# 3_CENR-40_PCA-10_NBU-1012_PWF_SIMMER_EMM.net
KiCad netlist of a schematic drawn in Altium Designer
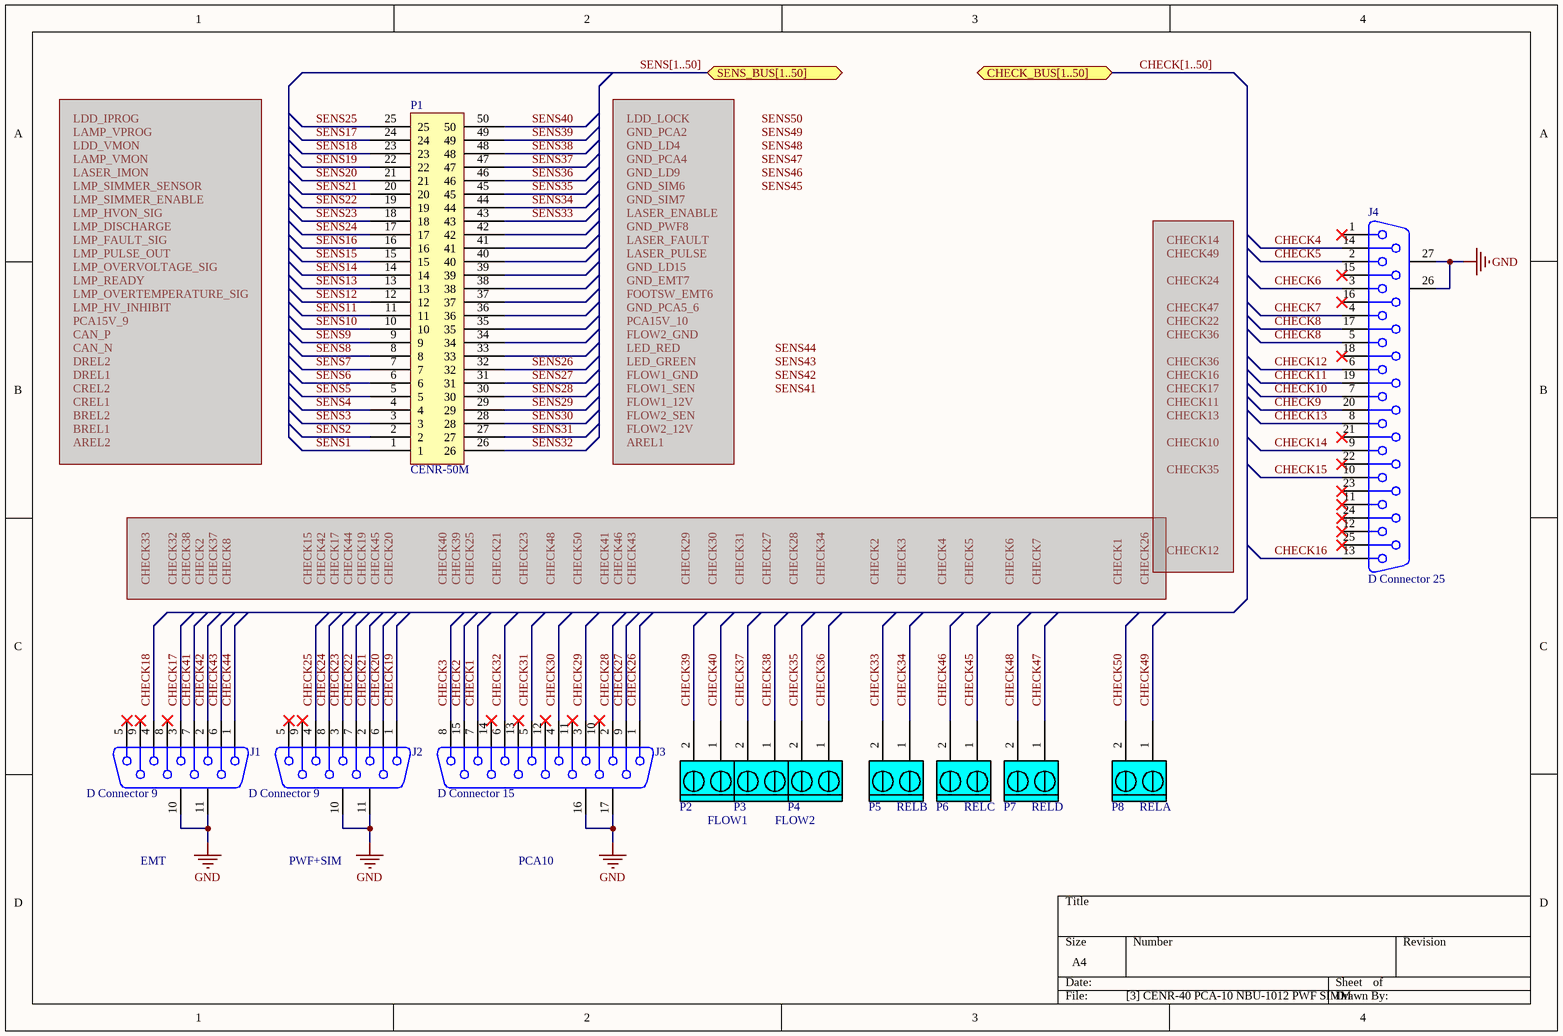
[diagram p0: [3] CENR-40 PCA-10 NBU-1012 PWF SIMMER EMMITER.SchDoc]

(export (version "E")
  (design (tool "Eeschema 10.0.6"))
  (components
    (comp (ref "J1")
      (value "D Connector 9")
      (footprint "DSUB1.385-2H9F")
      (description "Receptacle Assembly, 9 Position, Right Angle")
      (fields (field (name "PUBLISHER") "Altium Limited"))
      (libsource (lib "Connectors") (part "D Connector 9"))
    )
    (comp (ref "J2")
      (value "D Connector 9")
      (footprint "DSUB1.385-2H9M")
      (description "Receptacle Assembly, 9 Position, Right Angle")
      (fields (field (name "PUBLISHER") "Altium Limited"))
      (libsource (lib "Connectors") (part "D Connector 9"))
    )
    (comp (ref "J3")
      (value "D Connector 15")
      (footprint "DSUB1.385-2H15M")
      (description "Receptacle Assembly, 15 Position, Right Angle")
      (fields (field (name "PUBLISHER") "Altium Limited"))
      (libsource (lib "Connectors") (part "D Connector 15"))
    )
    (comp (ref "J4")
      (value "D Connector 25")
      (footprint "DSUB1.385-2H25A-F")
      (description "Receptacle Assembly, 25 Position, Right Angle")
      (fields (field (name "PUBLISHER") "Altium Limited"))
      (libsource (lib "Connectors") (part "D Connector 25"))
    )
    (comp (ref "P1")
      (value "CENR-50M")
      (footprint "CENR-50M")
      (libsource (lib "Connectors") (part "CENR-50M"))
    )
    (comp (ref "P2")
      (value "DG340-3.81")
      (footprint "DG340-3.81-02P-00A(H)")
      (description "Terminal block")
      (libsource (lib "Connectors") (part "DG340-3.81-02P"))
    )
    (comp (ref "P3")
      (value "DG340-3.81")
      (footprint "DG340-3.81-02P-00A(H)")
      (description "Terminal block")
      (libsource (lib "Connectors") (part "DG340-3.81-02P"))
    )
    (comp (ref "P4")
      (value "DG340-3.81")
      (footprint "DG340-3.81-02P-00A(H)")
      (description "Terminal block")
      (libsource (lib "Connectors") (part "DG340-3.81-02P"))
    )
    (comp (ref "P5")
      (value "DG340-3.81")
      (footprint "DG340-3.81-02P-00A(H)")
      (description "Terminal block")
      (libsource (lib "Connectors") (part "DG340-3.81-02P"))
    )
    (comp (ref "P6")
      (value "DG340-3.81")
      (footprint "DG340-3.81-02P-00A(H)")
      (description "Terminal block")
      (libsource (lib "Connectors") (part "DG340-3.81-02P"))
    )
    (comp (ref "P7")
      (value "DG340-3.81")
      (footprint "DG340-3.81-02P-00A(H)")
      (description "Terminal block")
      (libsource (lib "Connectors") (part "DG340-3.81-02P"))
    )
    (comp (ref "P8")
      (value "DG340-3.81")
      (footprint "DG340-3.81-02P-00A(H)")
      (description "Terminal block")
      (libsource (lib "Connectors") (part "DG340-3.81-02P"))
    )
  )
  (nets
    (net (code "7") (name "/CHECK1") (class "Default")
      (node (ref "J3") (pin "7") (pinfunction "7_7") (pintype "passive"))
    )
    (net (code "8") (name "/CHECK2") (class "Default")
      (node (ref "J3") (pin "15") (pinfunction "15_15") (pintype "passive"))
    )
    (net (code "9") (name "/CHECK3") (class "Default")
      (node (ref "J3") (pin "8") (pinfunction "8_8") (pintype "passive"))
    )
    (net (code "10") (name "/CHECK4") (class "Default")
      (node (ref "J4") (pin "14") (pinfunction "14_14") (pintype "passive"))
    )
    (net (code "11") (name "/CHECK5") (class "Default")
      (node (ref "J4") (pin "2") (pinfunction "2_2") (pintype "passive"))
    )
    (net (code "12") (name "/CHECK6") (class "Default")
      (node (ref "J4") (pin "3") (pinfunction "3_3") (pintype "passive"))
    )
    (net (code "13") (name "/CHECK7") (class "Default")
      (node (ref "J4") (pin "4") (pinfunction "4_4") (pintype "passive"))
    )
    (net (code "14") (name "/CHECK8") (class "Default")
      (node (ref "J4") (pin "17") (pinfunction "17_17") (pintype "passive"))
      (node (ref "J4") (pin "5") (pinfunction "5_5") (pintype "passive"))
    )
    (net (code "15") (name "/CHECK9") (class "Default")
      (node (ref "J4") (pin "20") (pinfunction "20_20") (pintype "passive"))
    )
    (net (code "16") (name "/CHECK10") (class "Default")
      (node (ref "J4") (pin "7") (pinfunction "7_7") (pintype "passive"))
    )
    (net (code "17") (name "/CHECK11") (class "Default")
      (node (ref "J4") (pin "19") (pinfunction "19_19") (pintype "passive"))
    )
    (net (code "18") (name "/CHECK12") (class "Default")
      (node (ref "J4") (pin "6") (pinfunction "6_6") (pintype "passive"))
    )
    (net (code "19") (name "/CHECK13") (class "Default")
      (node (ref "J4") (pin "8") (pinfunction "8_8") (pintype "passive"))
    )
    (net (code "20") (name "/CHECK14") (class "Default")
      (node (ref "J4") (pin "9") (pinfunction "9_9") (pintype "passive"))
    )
    (net (code "21") (name "/CHECK15") (class "Default")
      (node (ref "J4") (pin "10") (pinfunction "10_10") (pintype "passive"))
    )
    (net (code "22") (name "/CHECK16") (class "Default")
      (node (ref "J4") (pin "13") (pinfunction "13_13") (pintype "passive"))
    )
    (net (code "23") (name "/CHECK17") (class "Default")
      (node (ref "J1") (pin "3") (pinfunction "3_3") (pintype "passive"))
    )
    (net (code "24") (name "/CHECK18") (class "Default")
      (node (ref "J1") (pin "4") (pinfunction "4_4") (pintype "passive"))
    )
    (net (code "25") (name "/CHECK19") (class "Default")
      (node (ref "J2") (pin "1") (pinfunction "1_1") (pintype "passive"))
    )
    (net (code "26") (name "/CHECK20") (class "Default")
      (node (ref "J2") (pin "6") (pinfunction "6_6") (pintype "passive"))
    )
    (net (code "27") (name "/CHECK21") (class "Default")
      (node (ref "J2") (pin "2") (pinfunction "2_2") (pintype "passive"))
    )
    (net (code "28") (name "/CHECK22") (class "Default")
      (node (ref "J2") (pin "7") (pinfunction "7_7") (pintype "passive"))
    )
    (net (code "29") (name "/CHECK23") (class "Default")
      (node (ref "J2") (pin "3") (pinfunction "3_3") (pintype "passive"))
    )
    (net (code "30") (name "/CHECK24") (class "Default")
      (node (ref "J2") (pin "8") (pinfunction "8_8") (pintype "passive"))
    )
    (net (code "31") (name "/CHECK25") (class "Default")
      (node (ref "J2") (pin "4") (pinfunction "4_4") (pintype "passive"))
    )
    (net (code "32") (name "/CHECK26") (class "Default")
      (node (ref "J3") (pin "1") (pinfunction "1_1") (pintype "passive"))
    )
    (net (code "33") (name "/CHECK27") (class "Default")
      (node (ref "J3") (pin "9") (pinfunction "9_9") (pintype "passive"))
    )
    (net (code "34") (name "/CHECK28") (class "Default")
      (node (ref "J3") (pin "2") (pinfunction "2_2") (pintype "passive"))
    )
    (net (code "35") (name "/CHECK29") (class "Default")
      (node (ref "J3") (pin "3") (pinfunction "3_3") (pintype "passive"))
    )
    (net (code "36") (name "/CHECK30") (class "Default")
      (node (ref "J3") (pin "4") (pinfunction "4_4") (pintype "passive"))
    )
    (net (code "37") (name "/CHECK31") (class "Default")
      (node (ref "J3") (pin "5") (pinfunction "5_5") (pintype "passive"))
    )
    (net (code "38") (name "/CHECK32") (class "Default")
      (node (ref "J3") (pin "6") (pinfunction "6_6") (pintype "passive"))
    )
    (net (code "39") (name "/CHECK33") (class "Default")
      (node (ref "P5") (pin "2") (pinfunction "2_2") (pintype "passive"))
    )
    (net (code "40") (name "/CHECK34") (class "Default")
      (node (ref "P5") (pin "1") (pinfunction "1_1") (pintype "passive"))
    )
    (net (code "41") (name "/CHECK35") (class "Default")
      (node (ref "P4") (pin "2") (pinfunction "2_2") (pintype "passive"))
    )
    (net (code "42") (name "/CHECK36") (class "Default")
      (node (ref "P4") (pin "1") (pinfunction "1_1") (pintype "passive"))
    )
    (net (code "43") (name "/CHECK37") (class "Default")
      (node (ref "P3") (pin "2") (pinfunction "2_2") (pintype "passive"))
    )
    (net (code "44") (name "/CHECK38") (class "Default")
      (node (ref "P3") (pin "1") (pinfunction "1_1") (pintype "passive"))
    )
    (net (code "45") (name "/CHECK39") (class "Default")
      (node (ref "P2") (pin "2") (pinfunction "2_2") (pintype "passive"))
    )
    (net (code "46") (name "/CHECK40") (class "Default")
      (node (ref "P2") (pin "1") (pinfunction "1_1") (pintype "passive"))
    )
    (net (code "47") (name "/CHECK41") (class "Default")
      (node (ref "J1") (pin "7") (pinfunction "7_7") (pintype "passive"))
    )
    (net (code "48") (name "/CHECK42") (class "Default")
      (node (ref "J1") (pin "2") (pinfunction "2_2") (pintype "passive"))
    )
    (net (code "49") (name "/CHECK43") (class "Default")
      (node (ref "J1") (pin "6") (pinfunction "6_6") (pintype "passive"))
    )
    (net (code "50") (name "/CHECK44") (class "Default")
      (node (ref "J1") (pin "1") (pinfunction "1_1") (pintype "passive"))
    )
    (net (code "51") (name "/CHECK45") (class "Default")
      (node (ref "P6") (pin "1") (pinfunction "1_1") (pintype "passive"))
    )
    (net (code "52") (name "/CHECK46") (class "Default")
      (node (ref "P6") (pin "2") (pinfunction "2_2") (pintype "passive"))
    )
    (net (code "53") (name "/CHECK47") (class "Default")
      (node (ref "P7") (pin "1") (pinfunction "1_1") (pintype "passive"))
    )
    (net (code "54") (name "/CHECK48") (class "Default")
      (node (ref "P7") (pin "2") (pinfunction "2_2") (pintype "passive"))
    )
    (net (code "55") (name "/CHECK49") (class "Default")
      (node (ref "P8") (pin "1") (pinfunction "1_1") (pintype "passive"))
    )
    (net (code "56") (name "/CHECK50") (class "Default")
      (node (ref "P8") (pin "2") (pinfunction "2_2") (pintype "passive"))
    )
    (net (code "102") (name "/SENS1") (class "Default")
      (node (ref "P1") (pin "1") (pinfunction "1_1") (pintype "passive"))
    )
    (net (code "103") (name "/SENS2") (class "Default")
      (node (ref "P1") (pin "2") (pinfunction "2_2") (pintype "passive"))
    )
    (net (code "104") (name "/SENS3") (class "Default")
      (node (ref "P1") (pin "3") (pinfunction "3_3") (pintype "passive"))
    )
    (net (code "105") (name "/SENS4") (class "Default")
      (node (ref "P1") (pin "4") (pinfunction "4_4") (pintype "passive"))
    )
    (net (code "106") (name "/SENS5") (class "Default")
      (node (ref "P1") (pin "5") (pinfunction "5_5") (pintype "passive"))
    )
    (net (code "107") (name "/SENS6") (class "Default")
      (node (ref "P1") (pin "6") (pinfunction "6_6") (pintype "passive"))
    )
    (net (code "108") (name "/SENS7") (class "Default")
      (node (ref "P1") (pin "7") (pinfunction "7_7") (pintype "passive"))
    )
    (net (code "109") (name "/SENS8") (class "Default")
      (node (ref "P1") (pin "8") (pinfunction "8_8") (pintype "passive"))
    )
    (net (code "110") (name "/SENS9") (class "Default")
      (node (ref "P1") (pin "9") (pinfunction "9_9") (pintype "passive"))
    )
    (net (code "111") (name "/SENS10") (class "Default")
      (node (ref "P1") (pin "10") (pinfunction "10_10") (pintype "passive"))
    )
    (net (code "112") (name "/SENS11") (class "Default")
      (node (ref "P1") (pin "11") (pinfunction "11_11") (pintype "passive"))
    )
    (net (code "113") (name "/SENS12") (class "Default")
      (node (ref "P1") (pin "12") (pinfunction "12_12") (pintype "passive"))
    )
    (net (code "114") (name "/SENS13") (class "Default")
      (node (ref "P1") (pin "13") (pinfunction "13_13") (pintype "passive"))
    )
    (net (code "115") (name "/SENS14") (class "Default")
      (node (ref "P1") (pin "14") (pinfunction "14_14") (pintype "passive"))
    )
    (net (code "116") (name "/SENS15") (class "Default")
      (node (ref "P1") (pin "15") (pinfunction "15_15") (pintype "passive"))
    )
    (net (code "117") (name "/SENS16") (class "Default")
      (node (ref "P1") (pin "16") (pinfunction "16_16") (pintype "passive"))
    )
    (net (code "118") (name "/SENS17") (class "Default")
      (node (ref "P1") (pin "24") (pinfunction "24_24") (pintype "passive"))
    )
    (net (code "119") (name "/SENS18") (class "Default")
      (node (ref "P1") (pin "23") (pinfunction "23_23") (pintype "passive"))
    )
    (net (code "120") (name "/SENS19") (class "Default")
      (node (ref "P1") (pin "22") (pinfunction "22_22") (pintype "passive"))
    )
    (net (code "121") (name "/SENS20") (class "Default")
      (node (ref "P1") (pin "21") (pinfunction "21_21") (pintype "passive"))
    )
    (net (code "122") (name "/SENS21") (class "Default")
      (node (ref "P1") (pin "20") (pinfunction "20_20") (pintype "passive"))
    )
    (net (code "123") (name "/SENS22") (class "Default")
      (node (ref "P1") (pin "19") (pinfunction "19_19") (pintype "passive"))
    )
    (net (code "124") (name "/SENS23") (class "Default")
      (node (ref "P1") (pin "18") (pinfunction "18_18") (pintype "passive"))
    )
    (net (code "125") (name "/SENS24") (class "Default")
      (node (ref "P1") (pin "17") (pinfunction "17_17") (pintype "passive"))
    )
    (net (code "126") (name "/SENS25") (class "Default")
      (node (ref "P1") (pin "25") (pinfunction "25_25") (pintype "passive"))
    )
    (net (code "127") (name "/SENS26") (class "Default")
      (node (ref "P1") (pin "32") (pinfunction "32_32") (pintype "passive"))
    )
    (net (code "128") (name "/SENS27") (class "Default")
      (node (ref "P1") (pin "31") (pinfunction "31_31") (pintype "passive"))
    )
    (net (code "129") (name "/SENS28") (class "Default")
      (node (ref "P1") (pin "30") (pinfunction "30_30") (pintype "passive"))
    )
    (net (code "130") (name "/SENS29") (class "Default")
      (node (ref "P1") (pin "29") (pinfunction "29_29") (pintype "passive"))
    )
    (net (code "131") (name "/SENS30") (class "Default")
      (node (ref "P1") (pin "28") (pinfunction "28_28") (pintype "passive"))
    )
    (net (code "132") (name "/SENS31") (class "Default")
      (node (ref "P1") (pin "27") (pinfunction "27_27") (pintype "passive"))
    )
    (net (code "133") (name "/SENS32") (class "Default")
      (node (ref "P1") (pin "26") (pinfunction "26_26") (pintype "passive"))
    )
    (net (code "134") (name "/SENS33") (class "Default")
      (node (ref "P1") (pin "43") (pinfunction "43_43") (pintype "passive"))
    )
    (net (code "135") (name "/SENS34") (class "Default")
      (node (ref "P1") (pin "44") (pinfunction "44_44") (pintype "passive"))
    )
    (net (code "136") (name "/SENS35") (class "Default")
      (node (ref "P1") (pin "45") (pinfunction "45_45") (pintype "passive"))
    )
    (net (code "137") (name "/SENS36") (class "Default")
      (node (ref "P1") (pin "46") (pinfunction "46_46") (pintype "passive"))
    )
    (net (code "138") (name "/SENS37") (class "Default")
      (node (ref "P1") (pin "47") (pinfunction "47_47") (pintype "passive"))
    )
    (net (code "139") (name "/SENS38") (class "Default")
      (node (ref "P1") (pin "48") (pinfunction "48_48") (pintype "passive"))
    )
    (net (code "140") (name "/SENS39") (class "Default")
      (node (ref "P1") (pin "49") (pinfunction "49_49") (pintype "passive"))
    )
    (net (code "141") (name "/SENS40") (class "Default")
      (node (ref "P1") (pin "50") (pinfunction "50_50") (pintype "passive"))
    )
    (net (code "153") (name "GND") (class "Default")
      (node (ref "J1") (pin "10") (pinfunction "MH1_10") (pintype "passive"))
      (node (ref "J1") (pin "11") (pinfunction "MH2_11") (pintype "passive"))
      (node (ref "J2") (pin "10") (pinfunction "MH1_10") (pintype "passive"))
      (node (ref "J2") (pin "11") (pinfunction "MH2_11") (pintype "passive"))
      (node (ref "J3") (pin "16") (pinfunction "MH1_16") (pintype "passive"))
      (node (ref "J3") (pin "17") (pinfunction "MH2_17") (pintype "passive"))
      (node (ref "J4") (pin "26") (pinfunction "MH1_26") (pintype "passive"))
      (node (ref "J4") (pin "27") (pinfunction "MH2_27") (pintype "passive"))
    )
    (net (code "154") (name "unconnected-(J1-Pad5)") (class "Default")
      (node (ref "J1") (pin "5") (pinfunction "5_5") (pintype "passive+no_connect"))
    )
    (net (code "155") (name "unconnected-(J1-Pad8)") (class "Default")
      (node (ref "J1") (pin "8") (pinfunction "8_8") (pintype "passive+no_connect"))
    )
    (net (code "156") (name "unconnected-(J1-Pad9)") (class "Default")
      (node (ref "J1") (pin "9") (pinfunction "9_9") (pintype "passive+no_connect"))
    )
    (net (code "157") (name "unconnected-(J2-Pad5)") (class "Default")
      (node (ref "J2") (pin "5") (pinfunction "5_5") (pintype "passive+no_connect"))
    )
    (net (code "158") (name "unconnected-(J2-Pad9)") (class "Default")
      (node (ref "J2") (pin "9") (pinfunction "9_9") (pintype "passive+no_connect"))
    )
    (net (code "159") (name "unconnected-(J3-Pad10)") (class "Default")
      (node (ref "J3") (pin "10") (pinfunction "10_10") (pintype "passive+no_connect"))
    )
    (net (code "160") (name "unconnected-(J3-Pad11)") (class "Default")
      (node (ref "J3") (pin "11") (pinfunction "11_11") (pintype "passive+no_connect"))
    )
    (net (code "161") (name "unconnected-(J3-Pad12)") (class "Default")
      (node (ref "J3") (pin "12") (pinfunction "12_12") (pintype "passive+no_connect"))
    )
    (net (code "162") (name "unconnected-(J3-Pad13)") (class "Default")
      (node (ref "J3") (pin "13") (pinfunction "13_13") (pintype "passive+no_connect"))
    )
    (net (code "163") (name "unconnected-(J3-Pad14)") (class "Default")
      (node (ref "J3") (pin "14") (pinfunction "14_14") (pintype "passive+no_connect"))
    )
    (net (code "164") (name "unconnected-(J4-Pad1)") (class "Default")
      (node (ref "J4") (pin "1") (pinfunction "1_1") (pintype "passive+no_connect"))
    )
    (net (code "165") (name "unconnected-(J4-Pad11)") (class "Default")
      (node (ref "J4") (pin "11") (pinfunction "11_11") (pintype "passive+no_connect"))
    )
    (net (code "166") (name "unconnected-(J4-Pad12)") (class "Default")
      (node (ref "J4") (pin "12") (pinfunction "12_12") (pintype "passive+no_connect"))
    )
    (net (code "167") (name "unconnected-(J4-Pad15)") (class "Default")
      (node (ref "J4") (pin "15") (pinfunction "15_15") (pintype "passive+no_connect"))
    )
    (net (code "168") (name "unconnected-(J4-Pad16)") (class "Default")
      (node (ref "J4") (pin "16") (pinfunction "16_16") (pintype "passive+no_connect"))
    )
    (net (code "169") (name "unconnected-(J4-Pad18)") (class "Default")
      (node (ref "J4") (pin "18") (pinfunction "18_18") (pintype "passive+no_connect"))
    )
    (net (code "170") (name "unconnected-(J4-Pad21)") (class "Default")
      (node (ref "J4") (pin "21") (pinfunction "21_21") (pintype "passive+no_connect"))
    )
    (net (code "171") (name "unconnected-(J4-Pad22)") (class "Default")
      (node (ref "J4") (pin "22") (pinfunction "22_22") (pintype "passive+no_connect"))
    )
    (net (code "172") (name "unconnected-(J4-Pad23)") (class "Default")
      (node (ref "J4") (pin "23") (pinfunction "23_23") (pintype "passive+no_connect"))
    )
    (net (code "173") (name "unconnected-(J4-Pad24)") (class "Default")
      (node (ref "J4") (pin "24") (pinfunction "24_24") (pintype "passive+no_connect"))
    )
    (net (code "174") (name "unconnected-(J4-Pad25)") (class "Default")
      (node (ref "J4") (pin "25") (pinfunction "25_25") (pintype "passive+no_connect"))
    )
    (net (code "175") (name "unconnected-(P1-Pad33)") (class "Default")
      (node (ref "P1") (pin "33") (pinfunction "33_33") (pintype "passive"))
    )
    (net (code "176") (name "unconnected-(P1-Pad34)") (class "Default")
      (node (ref "P1") (pin "34") (pinfunction "34_34") (pintype "passive"))
    )
    (net (code "177") (name "unconnected-(P1-Pad35)") (class "Default")
      (node (ref "P1") (pin "35") (pinfunction "35_35") (pintype "passive"))
    )
    (net (code "178") (name "unconnected-(P1-Pad36)") (class "Default")
      (node (ref "P1") (pin "36") (pinfunction "36_36") (pintype "passive"))
    )
    (net (code "179") (name "unconnected-(P1-Pad37)") (class "Default")
      (node (ref "P1") (pin "37") (pinfunction "37_37") (pintype "passive"))
    )
    (net (code "180") (name "unconnected-(P1-Pad38)") (class "Default")
      (node (ref "P1") (pin "38") (pinfunction "38_38") (pintype "passive"))
    )
    (net (code "181") (name "unconnected-(P1-Pad39)") (class "Default")
      (node (ref "P1") (pin "39") (pinfunction "39_39") (pintype "passive"))
    )
    (net (code "182") (name "unconnected-(P1-Pad40)") (class "Default")
      (node (ref "P1") (pin "40") (pinfunction "40_40") (pintype "passive"))
    )
    (net (code "183") (name "unconnected-(P1-Pad41)") (class "Default")
      (node (ref "P1") (pin "41") (pinfunction "41_41") (pintype "passive"))
    )
    (net (code "184") (name "unconnected-(P1-Pad42)") (class "Default")
      (node (ref "P1") (pin "42") (pinfunction "42_42") (pintype "passive"))
    )
  )
)
